# ball_catch_order.net
KiCad netlist of a schematic drawn in EAGLE
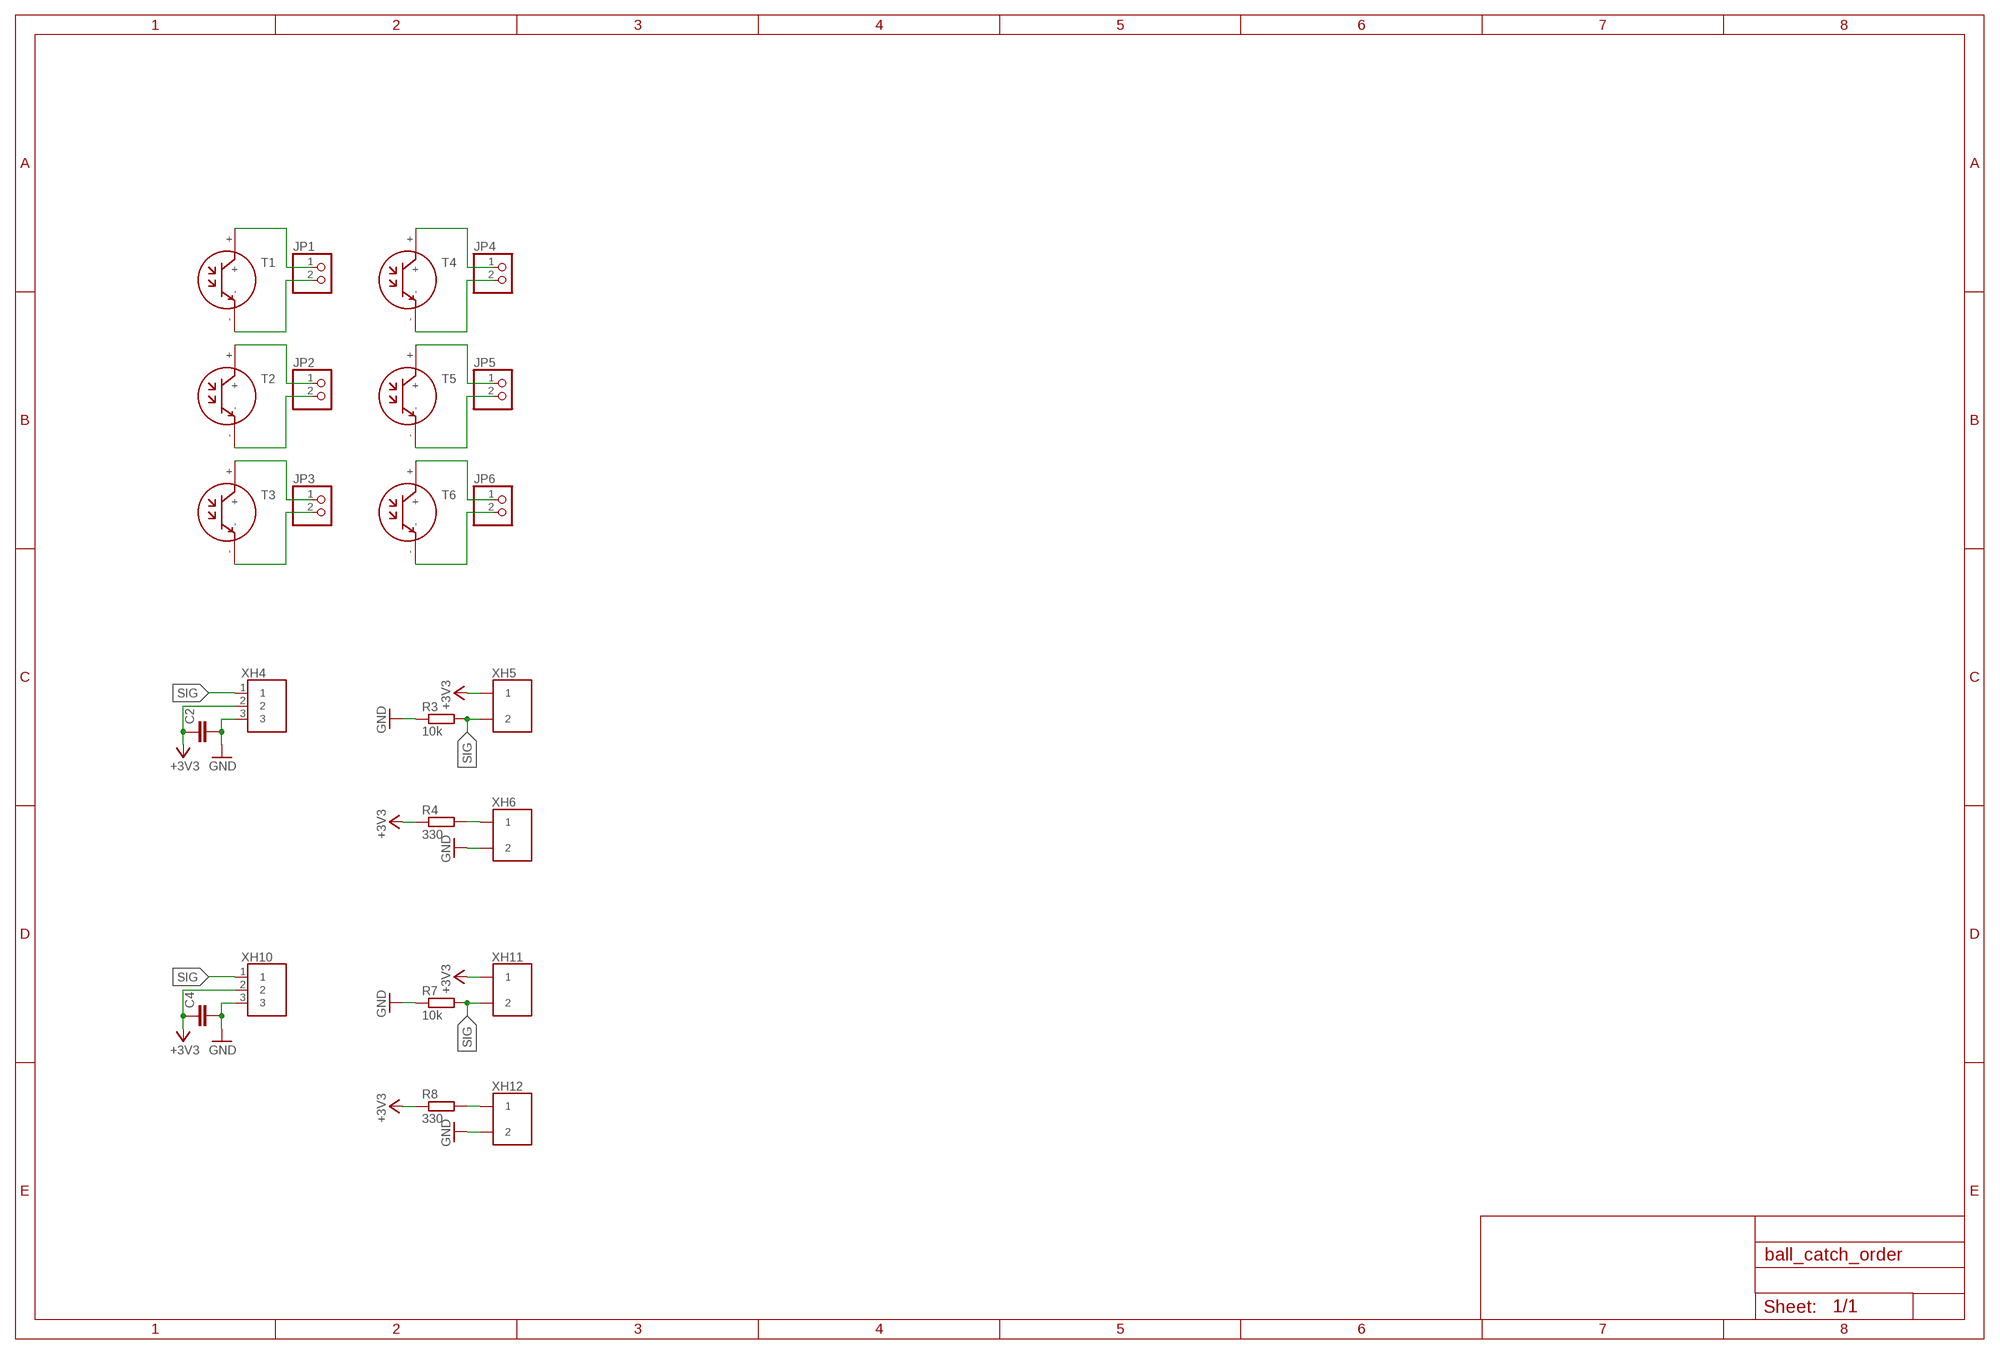
[diagram p0: schematic, sheet 1]

(export (version "E")
  (design (tool "Eeschema 10.0.6"))
  (components
    (comp (ref "C2")
      (value "C-EUC0603")
      (footprint "eagle-import:C0603")
      (libsource (lib "eagle-import") (part "C-EUC0603"))
    )
    (comp (ref "C4")
      (value "C-EUC0603")
      (footprint "eagle-import:C0603")
      (libsource (lib "eagle-import") (part "C-EUC0603"))
    )
    (comp (ref "JP1")
      (value "PINHD-1X2")
      (footprint "eagle-import:1X02")
      (libsource (lib "eagle-import") (part "PINHD-1X2"))
    )
    (comp (ref "JP2")
      (value "PINHD-1X2")
      (footprint "eagle-import:1X02")
      (libsource (lib "eagle-import") (part "PINHD-1X2"))
    )
    (comp (ref "JP3")
      (value "PINHD-1X2")
      (footprint "eagle-import:1X02")
      (libsource (lib "eagle-import") (part "PINHD-1X2"))
    )
    (comp (ref "JP4")
      (value "PINHD-1X2")
      (footprint "eagle-import:1X02")
      (libsource (lib "eagle-import") (part "PINHD-1X2"))
    )
    (comp (ref "JP5")
      (value "PINHD-1X2")
      (footprint "eagle-import:1X02")
      (libsource (lib "eagle-import") (part "PINHD-1X2"))
    )
    (comp (ref "JP6")
      (value "PINHD-1X2")
      (footprint "eagle-import:1X02")
      (libsource (lib "eagle-import") (part "PINHD-1X2"))
    )
    (comp (ref "R3")
      (value "10k")
      (footprint "eagle-import:0204_7")
      (libsource (lib "eagle-import") (part "R-EU_0204/7"))
    )
    (comp (ref "R4")
      (value "330")
      (footprint "eagle-import:0204_7")
      (libsource (lib "eagle-import") (part "R-EU_0204/7"))
    )
    (comp (ref "R7")
      (value "10k")
      (footprint "eagle-import:0204_7")
      (libsource (lib "eagle-import") (part "R-EU_0204/7"))
    )
    (comp (ref "R8")
      (value "330")
      (footprint "eagle-import:0204_7")
      (libsource (lib "eagle-import") (part "R-EU_0204/7"))
    )
    (comp (ref "T1")
      (value "NJL7302L-F3")
      (footprint "eagle-import:NJL7302L-F3")
      (libsource (lib "eagle-import") (part "NJL7302L-F3"))
    )
    (comp (ref "T2")
      (value "NJL7302L-F3")
      (footprint "eagle-import:NJL7302L-F3")
      (libsource (lib "eagle-import") (part "NJL7302L-F3"))
    )
    (comp (ref "T3")
      (value "NJL7302L-F3")
      (footprint "eagle-import:NJL7302L-F3")
      (libsource (lib "eagle-import") (part "NJL7302L-F3"))
    )
    (comp (ref "T4")
      (value "NJL7302L-F3")
      (footprint "eagle-import:NJL7302L-F3")
      (libsource (lib "eagle-import") (part "NJL7302L-F3"))
    )
    (comp (ref "T5")
      (value "NJL7302L-F3")
      (footprint "eagle-import:NJL7302L-F3")
      (libsource (lib "eagle-import") (part "NJL7302L-F3"))
    )
    (comp (ref "T6")
      (value "NJL7302L-F3")
      (footprint "eagle-import:NJL7302L-F3")
      (libsource (lib "eagle-import") (part "NJL7302L-F3"))
    )
    (comp (ref "XH4")
      (value "S3B")
      (footprint "eagle-import:S3B")
      (libsource (lib "eagle-import") (part "S3B"))
    )
    (comp (ref "XH5") (value "2B") (footprint "eagle-import:2B") (libsource (lib "eagle-import") (part "2B")))
    (comp (ref "XH6")
      (value "S2B")
      (footprint "eagle-import:S2B")
      (libsource (lib "eagle-import") (part "S2B"))
    )
    (comp (ref "XH10")
      (value "S3B")
      (footprint "eagle-import:S3B")
      (libsource (lib "eagle-import") (part "S3B"))
    )
    (comp (ref "XH11")
      (value "2B")
      (footprint "eagle-import:2B")
      (libsource (lib "eagle-import") (part "2B"))
    )
    (comp (ref "XH12")
      (value "S2B")
      (footprint "eagle-import:S2B")
      (libsource (lib "eagle-import") (part "S2B"))
    )
  )
  (nets
    (net (code "1") (name "+3V3") (class "Default")
      (node (ref "C2") (pin "1") (pinfunction "1_1") (pintype "passive"))
      (node (ref "C4") (pin "1") (pinfunction "1_1") (pintype "passive"))
      (node (ref "R4") (pin "1") (pinfunction "1_1") (pintype "passive"))
      (node (ref "R8") (pin "1") (pinfunction "1_1") (pintype "passive"))
      (node (ref "XH10") (pin "2") (pinfunction "2_2") (pintype "bidirectional"))
      (node (ref "XH11") (pin "1") (pinfunction "1_1") (pintype "bidirectional"))
      (node (ref "XH4") (pin "2") (pinfunction "2_2") (pintype "bidirectional"))
      (node (ref "XH5") (pin "1") (pinfunction "1_1") (pintype "bidirectional"))
    )
    (net (code "2") (name "GND") (class "Default")
      (node (ref "C2") (pin "2") (pinfunction "2_2") (pintype "passive"))
      (node (ref "C4") (pin "2") (pinfunction "2_2") (pintype "passive"))
      (node (ref "R3") (pin "1") (pinfunction "1_1") (pintype "passive"))
      (node (ref "R7") (pin "1") (pinfunction "1_1") (pintype "passive"))
      (node (ref "XH10") (pin "3") (pinfunction "3_3") (pintype "bidirectional"))
      (node (ref "XH12") (pin "2") (pinfunction "2_2") (pintype "bidirectional"))
      (node (ref "XH4") (pin "3") (pinfunction "3_3") (pintype "bidirectional"))
      (node (ref "XH6") (pin "2") (pinfunction "2_2") (pintype "bidirectional"))
    )
    (net (code "3") (name "Net-(JP1-Pad1)") (class "Default")
      (node (ref "JP1") (pin "1") (pinfunction "1_1") (pintype "passive"))
      (node (ref "T1") (pin "+") (pinfunction "+_+") (pintype "bidirectional"))
    )
    (net (code "4") (name "Net-(JP1-Pad2)") (class "Default")
      (node (ref "JP1") (pin "2") (pinfunction "2_2") (pintype "passive"))
      (node (ref "T1") (pin "-") (pinfunction "-_-") (pintype "bidirectional"))
    )
    (net (code "5") (name "Net-(JP2-Pad1)") (class "Default")
      (node (ref "JP2") (pin "1") (pinfunction "1_1") (pintype "passive"))
      (node (ref "T2") (pin "+") (pinfunction "+_+") (pintype "bidirectional"))
    )
    (net (code "6") (name "Net-(JP2-Pad2)") (class "Default")
      (node (ref "JP2") (pin "2") (pinfunction "2_2") (pintype "passive"))
      (node (ref "T2") (pin "-") (pinfunction "-_-") (pintype "bidirectional"))
    )
    (net (code "7") (name "Net-(JP3-Pad1)") (class "Default")
      (node (ref "JP3") (pin "1") (pinfunction "1_1") (pintype "passive"))
      (node (ref "T3") (pin "+") (pinfunction "+_+") (pintype "bidirectional"))
    )
    (net (code "8") (name "Net-(JP3-Pad2)") (class "Default")
      (node (ref "JP3") (pin "2") (pinfunction "2_2") (pintype "passive"))
      (node (ref "T3") (pin "-") (pinfunction "-_-") (pintype "bidirectional"))
    )
    (net (code "9") (name "Net-(JP4-Pad1)") (class "Default")
      (node (ref "JP4") (pin "1") (pinfunction "1_1") (pintype "passive"))
      (node (ref "T4") (pin "+") (pinfunction "+_+") (pintype "bidirectional"))
    )
    (net (code "10") (name "Net-(JP4-Pad2)") (class "Default")
      (node (ref "JP4") (pin "2") (pinfunction "2_2") (pintype "passive"))
      (node (ref "T4") (pin "-") (pinfunction "-_-") (pintype "bidirectional"))
    )
    (net (code "11") (name "Net-(JP5-Pad1)") (class "Default")
      (node (ref "JP5") (pin "1") (pinfunction "1_1") (pintype "passive"))
      (node (ref "T5") (pin "+") (pinfunction "+_+") (pintype "bidirectional"))
    )
    (net (code "12") (name "Net-(JP5-Pad2)") (class "Default")
      (node (ref "JP5") (pin "2") (pinfunction "2_2") (pintype "passive"))
      (node (ref "T5") (pin "-") (pinfunction "-_-") (pintype "bidirectional"))
    )
    (net (code "13") (name "Net-(JP6-Pad1)") (class "Default")
      (node (ref "JP6") (pin "1") (pinfunction "1_1") (pintype "passive"))
      (node (ref "T6") (pin "+") (pinfunction "+_+") (pintype "bidirectional"))
    )
    (net (code "14") (name "Net-(JP6-Pad2)") (class "Default")
      (node (ref "JP6") (pin "2") (pinfunction "2_2") (pintype "passive"))
      (node (ref "T6") (pin "-") (pinfunction "-_-") (pintype "bidirectional"))
    )
    (net (code "15") (name "Net-(R4-Pad2)") (class "Default")
      (node (ref "R4") (pin "2") (pinfunction "2_2") (pintype "passive"))
      (node (ref "XH6") (pin "1") (pinfunction "1_1") (pintype "bidirectional"))
    )
    (net (code "16") (name "Net-(R8-Pad2)") (class "Default")
      (node (ref "R8") (pin "2") (pinfunction "2_2") (pintype "passive"))
      (node (ref "XH12") (pin "1") (pinfunction "1_1") (pintype "bidirectional"))
    )
    (net (code "17") (name "SIG") (class "Default")
      (node (ref "R3") (pin "2") (pinfunction "2_2") (pintype "passive"))
      (node (ref "R7") (pin "2") (pinfunction "2_2") (pintype "passive"))
      (node (ref "XH10") (pin "1") (pinfunction "1_1") (pintype "bidirectional"))
      (node (ref "XH11") (pin "2") (pinfunction "2_2") (pintype "bidirectional"))
      (node (ref "XH4") (pin "1") (pinfunction "1_1") (pintype "bidirectional"))
      (node (ref "XH5") (pin "2") (pinfunction "2_2") (pintype "bidirectional"))
    )
  )
)
